# counter-test.net
KiCad netlist of a schematic drawn in EAGLE
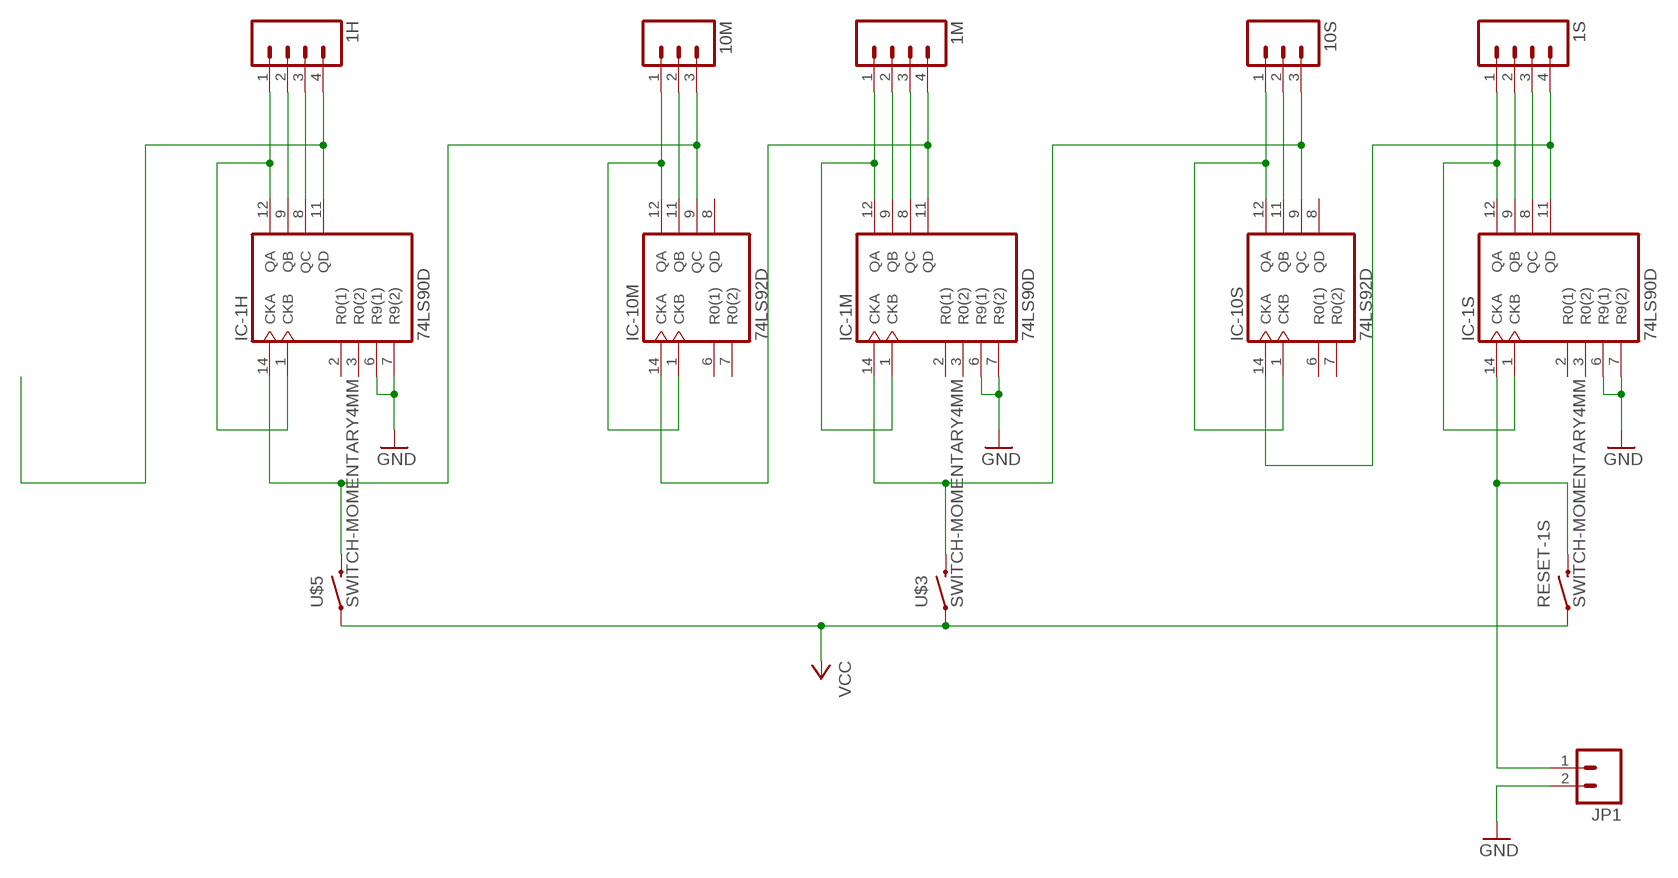
[diagram p0: schematic, sheet 1]

(export (version "E")
  (design (tool "Eeschema 10.0.6"))
  (components
    (comp (ref "1H")
      (value "M04PTH")
      (footprint "eagle-import:1X04")
      (libsource (lib "eagle-import") (part "M04PTH"))
    )
    (comp (ref "1M")
      (value "M04PTH")
      (footprint "eagle-import:1X04")
      (libsource (lib "eagle-import") (part "M04PTH"))
    )
    (comp (ref "1S")
      (value "M04PTH")
      (footprint "eagle-import:1X04")
      (libsource (lib "eagle-import") (part "M04PTH"))
    )
    (comp (ref "10M")
      (value "M03PTH")
      (footprint "eagle-import:1X03")
      (libsource (lib "eagle-import") (part "M03PTH"))
    )
    (comp (ref "10S")
      (value "M03PTH")
      (footprint "eagle-import:1X03")
      (libsource (lib "eagle-import") (part "M03PTH"))
    )
    (comp (ref "IC-1H")
      (value "74LS90D")
      (footprint "eagle-import:SO14")
      (libsource (lib "eagle-import") (part "7490DLS"))
    )
    (comp (ref "IC-1M")
      (value "74LS90D")
      (footprint "eagle-import:SO14")
      (libsource (lib "eagle-import") (part "7490DLS"))
    )
    (comp (ref "IC-1S")
      (value "74LS90D")
      (footprint "eagle-import:SO14")
      (libsource (lib "eagle-import") (part "7490DLS"))
    )
    (comp (ref "IC-10M")
      (value "74LS92D")
      (footprint "eagle-import:SO14")
      (libsource (lib "eagle-import") (part "7492DLS"))
    )
    (comp (ref "IC-10S")
      (value "74LS92D")
      (footprint "eagle-import:SO14")
      (libsource (lib "eagle-import") (part "7492DLS"))
    )
    (comp (ref "JP1")
      (value "M02PTH")
      (footprint "eagle-import:1X02")
      (libsource (lib "eagle-import") (part "M02PTH"))
    )
    (comp (ref "RESET-1S")
      (value "SWITCH-MOMENTARY4MM")
      (footprint "eagle-import:TACTILE_SWITCH_SMD")
      (libsource (lib "eagle-import") (part "SWITCH-MOMENTARY4MM"))
    )
    (comp (ref "U$3")
      (value "SWITCH-MOMENTARY4MM")
      (footprint "eagle-import:TACTILE_SWITCH_SMD")
      (libsource (lib "eagle-import") (part "SWITCH-MOMENTARY4MM"))
    )
    (comp (ref "U$5")
      (value "SWITCH-MOMENTARY4MM")
      (footprint "eagle-import:TACTILE_SWITCH_SMD")
      (libsource (lib "eagle-import") (part "SWITCH-MOMENTARY4MM"))
    )
  )
  (nets
    (net (code "1") (name "GND") (class "Default")
      (node (ref "IC-1H") (pin "6") (pinfunction "R9(1)_6") (pintype "input"))
      (node (ref "IC-1H") (pin "7") (pinfunction "R9(2)_7") (pintype "input"))
      (node (ref "IC-1M") (pin "6") (pinfunction "R9(1)_6") (pintype "input"))
      (node (ref "IC-1M") (pin "7") (pinfunction "R9(2)_7") (pintype "input"))
      (node (ref "IC-1S") (pin "6") (pinfunction "R9(1)_6") (pintype "input"))
      (node (ref "IC-1S") (pin "7") (pinfunction "R9(2)_7") (pintype "input"))
      (node (ref "JP1") (pin "2") (pinfunction "2_2") (pintype "passive"))
    )
    (net (code "2") (name "Net-(IC-1HA-CKB)") (class "Default")
      (node (ref "1H") (pin "1") (pinfunction "1_1") (pintype "passive"))
      (node (ref "IC-1H") (pin "1") (pinfunction "CKB_1") (pintype "input"))
      (node (ref "IC-1H") (pin "12") (pinfunction "QA_12") (pintype "output"))
    )
    (net (code "3") (name "Net-(IC-1HA-QB)") (class "Default")
      (node (ref "1H") (pin "2") (pinfunction "2_2") (pintype "passive"))
      (node (ref "IC-1H") (pin "9") (pinfunction "QB_9") (pintype "output"))
    )
    (net (code "4") (name "Net-(IC-1HA-QC)") (class "Default")
      (node (ref "1H") (pin "3") (pinfunction "3_3") (pintype "passive"))
      (node (ref "IC-1H") (pin "8") (pinfunction "QC_8") (pintype "output"))
    )
    (net (code "5") (name "Net-(IC-1HA-QD)") (class "Default")
      (node (ref "1H") (pin "4") (pinfunction "4_4") (pintype "passive"))
      (node (ref "IC-1H") (pin "11") (pinfunction "QD_11") (pintype "output"))
    )
    (net (code "6") (name "Net-(IC-1MA-CKB)") (class "Default")
      (node (ref "1M") (pin "1") (pinfunction "1_1") (pintype "passive"))
      (node (ref "IC-1M") (pin "1") (pinfunction "CKB_1") (pintype "input"))
      (node (ref "IC-1M") (pin "12") (pinfunction "QA_12") (pintype "output"))
    )
    (net (code "7") (name "Net-(IC-1MA-QB)") (class "Default")
      (node (ref "1M") (pin "2") (pinfunction "2_2") (pintype "passive"))
      (node (ref "IC-1M") (pin "9") (pinfunction "QB_9") (pintype "output"))
    )
    (net (code "8") (name "Net-(IC-1MA-QC)") (class "Default")
      (node (ref "1M") (pin "3") (pinfunction "3_3") (pintype "passive"))
      (node (ref "IC-1M") (pin "8") (pinfunction "QC_8") (pintype "output"))
    )
    (net (code "9") (name "Net-(IC-1SA-CKA)") (class "Default")
      (node (ref "IC-1S") (pin "14") (pinfunction "CKA_14") (pintype "input"))
      (node (ref "JP1") (pin "1") (pinfunction "1_1") (pintype "passive"))
      (node (ref "RESET-1S") (pin "3") (pinfunction "2_3") (pintype "passive"))
      (node (ref "RESET-1S") (pin "4") (pinfunction "2_4") (pintype "passive"))
    )
    (net (code "10") (name "Net-(IC-1SA-CKB)") (class "Default")
      (node (ref "1S") (pin "1") (pinfunction "1_1") (pintype "passive"))
      (node (ref "IC-1S") (pin "1") (pinfunction "CKB_1") (pintype "input"))
      (node (ref "IC-1S") (pin "12") (pinfunction "QA_12") (pintype "output"))
    )
    (net (code "11") (name "Net-(IC-1SA-QB)") (class "Default")
      (node (ref "1S") (pin "2") (pinfunction "2_2") (pintype "passive"))
      (node (ref "IC-1S") (pin "9") (pinfunction "QB_9") (pintype "output"))
    )
    (net (code "12") (name "Net-(IC-1SA-QC)") (class "Default")
      (node (ref "1S") (pin "3") (pinfunction "3_3") (pintype "passive"))
      (node (ref "IC-1S") (pin "8") (pinfunction "QC_8") (pintype "output"))
    )
    (net (code "13") (name "Net-(IC-10MA-CKA)") (class "Default")
      (node (ref "1M") (pin "4") (pinfunction "4_4") (pintype "passive"))
      (node (ref "IC-10M") (pin "14") (pinfunction "CKA_14") (pintype "input"))
      (node (ref "IC-1M") (pin "11") (pinfunction "QD_11") (pintype "output"))
    )
    (net (code "14") (name "Net-(IC-10MA-CKB)") (class "Default")
      (node (ref "10M") (pin "1") (pinfunction "1_1") (pintype "passive"))
      (node (ref "IC-10M") (pin "1") (pinfunction "CKB_1") (pintype "input"))
      (node (ref "IC-10M") (pin "12") (pinfunction "QA_12") (pintype "output"))
    )
    (net (code "15") (name "Net-(IC-10MA-QB)") (class "Default")
      (node (ref "10M") (pin "2") (pinfunction "2_2") (pintype "passive"))
      (node (ref "IC-10M") (pin "11") (pinfunction "QB_11") (pintype "output"))
    )
    (net (code "16") (name "Net-(IC-10MA-QC)") (class "Default")
      (node (ref "10M") (pin "3") (pinfunction "3_3") (pintype "passive"))
      (node (ref "IC-10M") (pin "9") (pinfunction "QC_9") (pintype "output"))
      (node (ref "IC-1H") (pin "14") (pinfunction "CKA_14") (pintype "input"))
      (node (ref "U$5") (pin "3") (pinfunction "2_3") (pintype "passive"))
      (node (ref "U$5") (pin "4") (pinfunction "2_4") (pintype "passive"))
    )
    (net (code "17") (name "Net-(IC-10SA-CKA)") (class "Default")
      (node (ref "1S") (pin "4") (pinfunction "4_4") (pintype "passive"))
      (node (ref "IC-10S") (pin "14") (pinfunction "CKA_14") (pintype "input"))
      (node (ref "IC-1S") (pin "11") (pinfunction "QD_11") (pintype "output"))
    )
    (net (code "18") (name "Net-(IC-10SA-CKB)") (class "Default")
      (node (ref "10S") (pin "1") (pinfunction "1_1") (pintype "passive"))
      (node (ref "IC-10S") (pin "1") (pinfunction "CKB_1") (pintype "input"))
      (node (ref "IC-10S") (pin "12") (pinfunction "QA_12") (pintype "output"))
    )
    (net (code "19") (name "Net-(IC-10SA-QB)") (class "Default")
      (node (ref "10S") (pin "2") (pinfunction "2_2") (pintype "passive"))
      (node (ref "IC-10S") (pin "11") (pinfunction "QB_11") (pintype "output"))
    )
    (net (code "20") (name "Net-(IC-10SA-QC)") (class "Default")
      (node (ref "10S") (pin "3") (pinfunction "3_3") (pintype "passive"))
      (node (ref "IC-10S") (pin "9") (pinfunction "QC_9") (pintype "output"))
      (node (ref "IC-1M") (pin "14") (pinfunction "CKA_14") (pintype "input"))
      (node (ref "U$3") (pin "3") (pinfunction "2_3") (pintype "passive"))
      (node (ref "U$3") (pin "4") (pinfunction "2_4") (pintype "passive"))
    )
    (net (code "21") (name "VCC") (class "Default")
      (node (ref "RESET-1S") (pin "1") (pinfunction "1_1") (pintype "passive"))
      (node (ref "RESET-1S") (pin "2") (pinfunction "1_2") (pintype "passive"))
      (node (ref "U$3") (pin "1") (pinfunction "1_1") (pintype "passive"))
      (node (ref "U$3") (pin "2") (pinfunction "1_2") (pintype "passive"))
      (node (ref "U$5") (pin "1") (pinfunction "1_1") (pintype "passive"))
      (node (ref "U$5") (pin "2") (pinfunction "1_2") (pintype "passive"))
    )
    (net (code "22") (name "unconnected-(IC-1HA-R0(1)-Pad2)") (class "Default")
      (node (ref "IC-1H") (pin "2") (pinfunction "R0(1)_2") (pintype "input"))
    )
    (net (code "23") (name "unconnected-(IC-1HA-R0(2)-Pad3)") (class "Default")
      (node (ref "IC-1H") (pin "3") (pinfunction "R0(2)_3") (pintype "input"))
    )
    (net (code "24") (name "unconnected-(IC-1MA-R0(1)-Pad2)") (class "Default")
      (node (ref "IC-1M") (pin "2") (pinfunction "R0(1)_2") (pintype "input"))
    )
    (net (code "25") (name "unconnected-(IC-1MA-R0(2)-Pad3)") (class "Default")
      (node (ref "IC-1M") (pin "3") (pinfunction "R0(2)_3") (pintype "input"))
    )
    (net (code "26") (name "unconnected-(IC-1SA-R0(1)-Pad2)") (class "Default")
      (node (ref "IC-1S") (pin "2") (pinfunction "R0(1)_2") (pintype "input"))
    )
    (net (code "27") (name "unconnected-(IC-1SA-R0(2)-Pad3)") (class "Default")
      (node (ref "IC-1S") (pin "3") (pinfunction "R0(2)_3") (pintype "input"))
    )
    (net (code "28") (name "unconnected-(IC-10MA-QD-Pad8)") (class "Default")
      (node (ref "IC-10M") (pin "8") (pinfunction "QD_8") (pintype "output"))
    )
    (net (code "29") (name "unconnected-(IC-10MA-R0(1)-Pad6)") (class "Default")
      (node (ref "IC-10M") (pin "6") (pinfunction "R0(1)_6") (pintype "input"))
    )
    (net (code "30") (name "unconnected-(IC-10MA-R0(2)-Pad7)") (class "Default")
      (node (ref "IC-10M") (pin "7") (pinfunction "R0(2)_7") (pintype "input"))
    )
    (net (code "31") (name "unconnected-(IC-10SA-QD-Pad8)") (class "Default")
      (node (ref "IC-10S") (pin "8") (pinfunction "QD_8") (pintype "output"))
    )
    (net (code "32") (name "unconnected-(IC-10SA-R0(1)-Pad6)") (class "Default")
      (node (ref "IC-10S") (pin "6") (pinfunction "R0(1)_6") (pintype "input"))
    )
    (net (code "33") (name "unconnected-(IC-10SA-R0(2)-Pad7)") (class "Default")
      (node (ref "IC-10S") (pin "7") (pinfunction "R0(2)_7") (pintype "input"))
    )
  )
)
